# ESC_B.net
KiCad netlist of a schematic drawn in Altium Designer
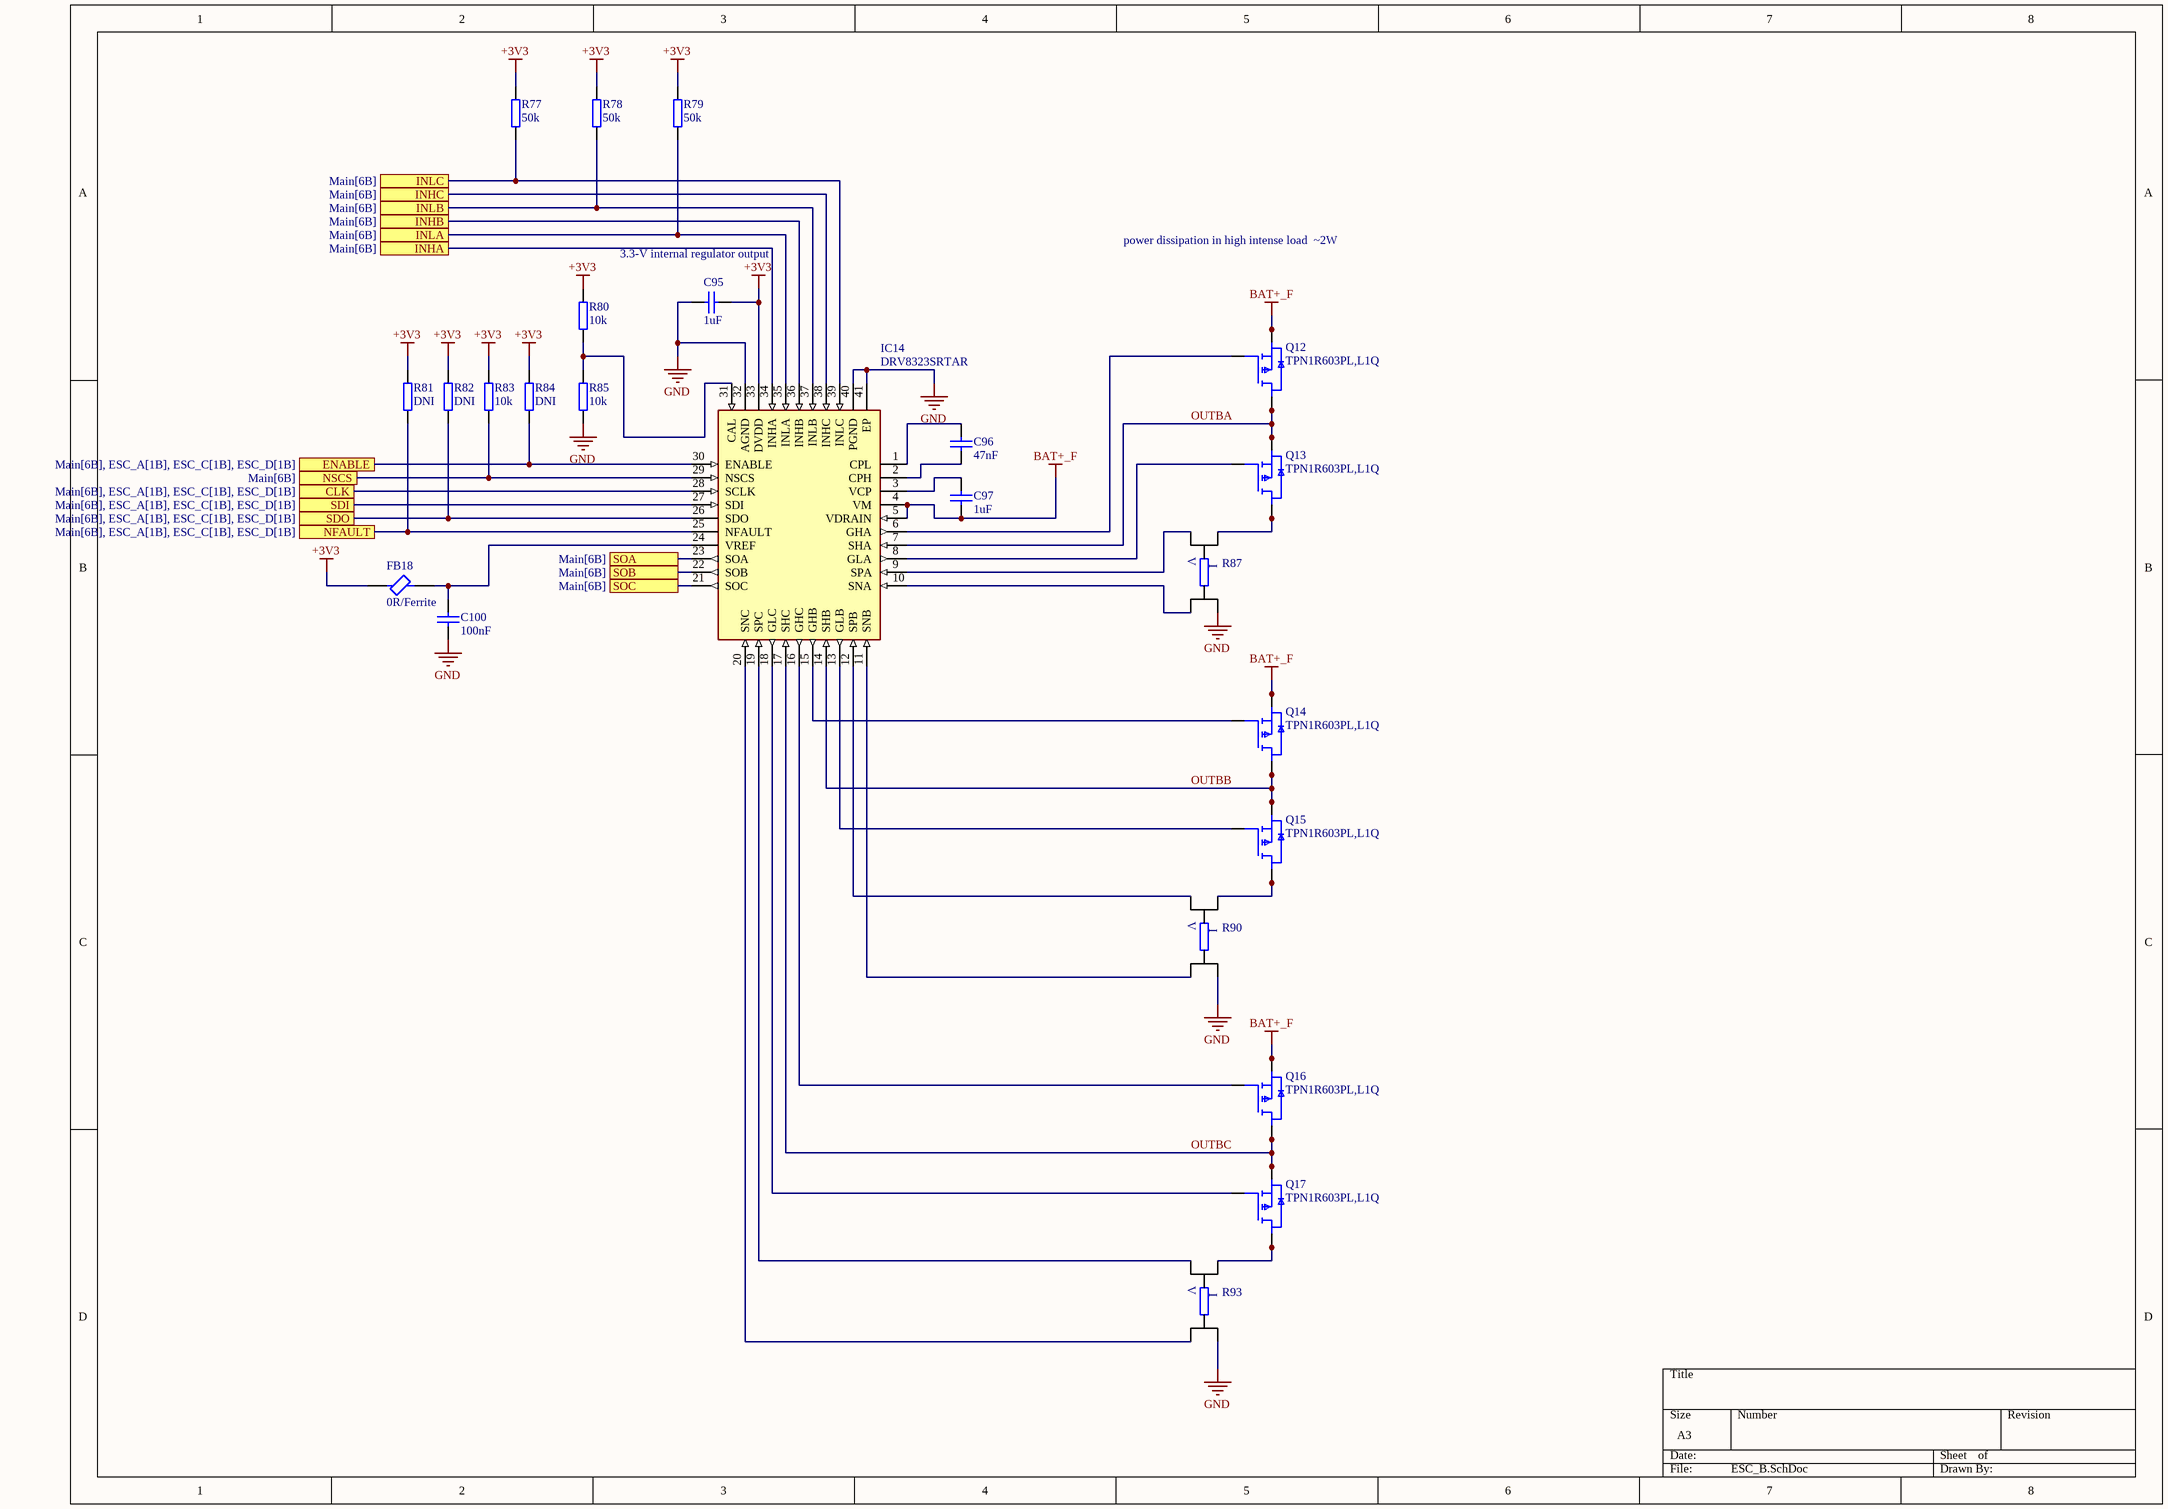
[diagram p0: ESC_B.SchDoc]

(export (version "E")
  (design (tool "Eeschema 10.0.6"))
  (components
    (comp (ref "C95")
      (value "1uF")
      (footprint "CAP0402")
      (fields (field (name "VOLTAGE") "val") (field (name "Comment") "Cap0402"))
      (libsource (lib "capacitorsSMD") (part "Cap0402"))
    )
    (comp (ref "C96")
      (value "47nF")
      (footprint "CAP0603")
      (description "50V")
      (fields (field (name "Comment") "CapSMD0603") (field (name "PUBLISHER") "Altium Limited"))
      (libsource (lib "capacitorsSMD") (part "CapSMD0603"))
    )
    (comp (ref "C97")
      (value "1uF")
      (footprint "CAP0603")
      (description "50V")
      (fields (field (name "Comment") "CapSMD0603") (field (name "PUBLISHER") "Altium Limited"))
      (libsource (lib "capacitorsSMD") (part "CapSMD0603"))
    )
    (comp (ref "C100")
      (value "100nF")
      (footprint "CAP0402")
      (fields (field (name "VOLTAGE") "6V3") (field (name "Comment") "Cap0402"))
      (libsource (lib "capacitorsSMD") (part "Cap0402"))
    )
    (comp (ref "FB18")
      (value "0R/Ferrite")
      (footprint "SamacSys:NFZ15SG152SN10B")
      (description "Ferrite Bead")
      (fields
        (field (name "MANUFACTURER_PART_NUMBER") "BLM15PE471SH1D")
        (field (name "MOUSER PART NUMBER") "81-BLM15PE471SH1D")
      )
      (libsource (lib "SamacSys") (part "BLM15PE471SH1D"))
    )
    (comp (ref "IC14")
      (value "DRV8323SRTAR")
      (footprint "SamacSys:QFN50P600X600X80-41N-D")
      (description "Integrated Circuit")
      (fields (field (name "MOUSER PART NUMBER") "595-DRV8323SRTAR"))
      (libsource (lib "*") (part "DRV8323SRTAR"))
    )
    (comp (ref "Q12")
      (value "TPN1R603PL,L1Q")
      (footprint "SamacSys:TPN1R603PLL1Q")
      (description "MOSFET (N-Channel)")
      (fields (field (name "MOUSER PART NUMBER") "757-TPN1R603PLL1Q"))
      (libsource (lib "SamacSys") (part "TPN1R603PL,L1Q"))
    )
    (comp (ref "Q13")
      (value "TPN1R603PL,L1Q")
      (footprint "SamacSys:TPN1R603PLL1Q")
      (description "MOSFET (N-Channel)")
      (fields (field (name "MOUSER PART NUMBER") "757-TPN1R603PLL1Q"))
      (libsource (lib "SamacSys") (part "TPN1R603PL,L1Q"))
    )
    (comp (ref "Q14")
      (value "TPN1R603PL,L1Q")
      (footprint "SamacSys:TPN1R603PLL1Q")
      (description "MOSFET (N-Channel)")
      (fields (field (name "MOUSER PART NUMBER") "757-TPN1R603PLL1Q"))
      (libsource (lib "SamacSys") (part "TPN1R603PL,L1Q"))
    )
    (comp (ref "Q15")
      (value "TPN1R603PL,L1Q")
      (footprint "SamacSys:TPN1R603PLL1Q")
      (description "MOSFET (N-Channel)")
      (fields (field (name "MOUSER PART NUMBER") "757-TPN1R603PLL1Q"))
      (libsource (lib "SamacSys") (part "TPN1R603PL,L1Q"))
    )
    (comp (ref "Q16")
      (value "TPN1R603PL,L1Q")
      (footprint "SamacSys:TPN1R603PLL1Q")
      (description "MOSFET (N-Channel)")
      (fields (field (name "MOUSER PART NUMBER") "757-TPN1R603PLL1Q"))
      (libsource (lib "SamacSys") (part "TPN1R603PL,L1Q"))
    )
    (comp (ref "Q17")
      (value "TPN1R603PL,L1Q")
      (footprint "SamacSys:TPN1R603PLL1Q")
      (description "MOSFET (N-Channel)")
      (fields (field (name "MOUSER PART NUMBER") "757-TPN1R603PLL1Q"))
      (libsource (lib "SamacSys") (part "TPN1R603PL,L1Q"))
    )
    (comp (ref "R77")
      (value "50k")
      (footprint "RES0402")
      (fields (field (name "Comment") "Res0402"))
      (libsource (lib "resistorSMD") (part "Res0402"))
    )
    (comp (ref "R78")
      (value "50k")
      (footprint "RES0402")
      (fields (field (name "Comment") "Res0402"))
      (libsource (lib "resistorSMD") (part "Res0402"))
    )
    (comp (ref "R79")
      (value "50k")
      (footprint "RES0402")
      (fields (field (name "Comment") "Res0402"))
      (libsource (lib "resistorSMD") (part "Res0402"))
    )
    (comp (ref "R80")
      (value "10k")
      (footprint "RES0402")
      (fields (field (name "Comment") "Res0402"))
      (libsource (lib "resistorSMD") (part "Res0402"))
    )
    (comp (ref "R81")
      (value "DNI")
      (footprint "RES0402")
      (fields (field (name "Comment") "Res0402"))
      (libsource (lib "resistorSMD") (part "Res0402"))
    )
    (comp (ref "R82")
      (value "DNI")
      (footprint "RES0402")
      (fields (field (name "Comment") "Res0402"))
      (libsource (lib "resistorSMD") (part "Res0402"))
    )
    (comp (ref "R83")
      (value "10k")
      (footprint "RES0402")
      (fields (field (name "Comment") "Res0402"))
      (libsource (lib "resistorSMD") (part "Res0402"))
    )
    (comp (ref "R84")
      (value "DNI")
      (footprint "RES0402")
      (fields (field (name "Comment") "Res0402"))
      (libsource (lib "resistorSMD") (part "Res0402"))
    )
    (comp (ref "R85")
      (value "10k")
      (footprint "RES0402")
      (fields (field (name "Comment") "Res0402"))
      (libsource (lib "resistorSMD") (part "Res0402"))
    )
    (comp (ref "R87")
      (value "WSK12161L000FEA")
      (footprint "SamacSys:WSK12161L000FEA")
      (description "Resistor")
      (fields
        (field (name "MANUFACTURER_PART_NUMBER") "WSK1216L5000FEA")
        (field (name "MOUSER PART NUMBER") "71-WSK1216L5000FEA")
      )
      (libsource (lib "SamacSys") (part "WSK1216L5000FEA"))
    )
    (comp (ref "R90")
      (value "WSK12161L000FEA")
      (footprint "SamacSys:WSK12161L000FEA")
      (description "Resistor")
      (fields
        (field (name "MANUFACTURER_PART_NUMBER") "WSK1216L5000FEA")
        (field (name "MOUSER PART NUMBER") "71-WSK1216L5000FEA")
      )
      (libsource (lib "SamacSys") (part "WSK1216L5000FEA"))
    )
    (comp (ref "R93")
      (value "WSK12161L000FEA")
      (footprint "SamacSys:WSK12161L000FEA")
      (description "Resistor")
      (fields
        (field (name "MANUFACTURER_PART_NUMBER") "WSK1216L5000FEA")
        (field (name "MOUSER PART NUMBER") "71-WSK1216L5000FEA")
      )
      (libsource (lib "SamacSys") (part "WSK1216L5000FEA"))
    )
  )
  (nets
    (net (code "1") (name "+3V3") (class "Default")
      (node (ref "C95") (pin "2") (pinfunction "2_2") (pintype "passive"))
      (node (ref "FB18") (pin "1") (pinfunction "1_1") (pintype "passive"))
      (node (ref "IC14") (pin "33") (pinfunction "DVDD_33") (pintype "power_in"))
      (node (ref "R77") (pin "2") (pinfunction "2_2") (pintype "passive"))
      (node (ref "R78") (pin "2") (pinfunction "2_2") (pintype "passive"))
      (node (ref "R79") (pin "2") (pinfunction "2_2") (pintype "passive"))
      (node (ref "R80") (pin "2") (pinfunction "2_2") (pintype "passive"))
      (node (ref "R81") (pin "2") (pinfunction "2_2") (pintype "passive"))
      (node (ref "R82") (pin "2") (pinfunction "2_2") (pintype "passive"))
      (node (ref "R83") (pin "2") (pinfunction "2_2") (pintype "passive"))
      (node (ref "R84") (pin "2") (pinfunction "2_2") (pintype "passive"))
    )
    (net (code "2") (name "/CLK") (class "Default")
      (node (ref "IC14") (pin "28") (pinfunction "SCLK_28") (pintype "input"))
    )
    (net (code "3") (name "/ENABLE") (class "Default")
      (node (ref "IC14") (pin "30") (pinfunction "ENABLE_30") (pintype "input"))
      (node (ref "R84") (pin "1") (pinfunction "1_1") (pintype "passive"))
    )
    (net (code "4") (name "/INHA") (class "Default")
      (node (ref "IC14") (pin "34") (pinfunction "INHA_34") (pintype "input"))
    )
    (net (code "5") (name "/INHB") (class "Default")
      (node (ref "IC14") (pin "36") (pinfunction "INHB_36") (pintype "input"))
    )
    (net (code "6") (name "/INHC") (class "Default")
      (node (ref "IC14") (pin "38") (pinfunction "INHC_38") (pintype "input"))
    )
    (net (code "7") (name "/INLA") (class "Default")
      (node (ref "IC14") (pin "35") (pinfunction "INLA_35") (pintype "input"))
      (node (ref "R79") (pin "1") (pinfunction "1_1") (pintype "passive"))
    )
    (net (code "8") (name "/INLB") (class "Default")
      (node (ref "IC14") (pin "37") (pinfunction "INLB_37") (pintype "input"))
      (node (ref "R78") (pin "1") (pinfunction "1_1") (pintype "passive"))
    )
    (net (code "9") (name "/INLC") (class "Default")
      (node (ref "IC14") (pin "39") (pinfunction "INLC_39") (pintype "input"))
      (node (ref "R77") (pin "1") (pinfunction "1_1") (pintype "passive"))
    )
    (net (code "10") (name "/NFAULT") (class "Default")
      (node (ref "IC14") (pin "25") (pinfunction "NFAULT_25") (pintype "passive"))
      (node (ref "R81") (pin "1") (pinfunction "1_1") (pintype "passive"))
    )
    (net (code "11") (name "/NSCS") (class "Default")
      (node (ref "IC14") (pin "29") (pinfunction "NSCS_29") (pintype "input"))
      (node (ref "R83") (pin "1") (pinfunction "1_1") (pintype "passive"))
    )
    (net (code "12") (name "/OUTBA") (class "Default")
      (node (ref "IC14") (pin "7") (pinfunction "SHA_7") (pintype "input"))
      (node (ref "Q12") (pin "5") (pinfunction "D_1_5") (pintype "passive"))
      (node (ref "Q12") (pin "6") (pinfunction "D_2_6") (pintype "passive"))
      (node (ref "Q12") (pin "7") (pinfunction "D_3_7") (pintype "passive"))
      (node (ref "Q12") (pin "8") (pinfunction "D_4_8") (pintype "passive"))
      (node (ref "Q12") (pin "9") (pinfunction "D_4_9") (pintype "passive"))
      (node (ref "Q13") (pin "1") (pinfunction "S_1_1") (pintype "passive"))
      (node (ref "Q13") (pin "2") (pinfunction "S_2_2") (pintype "passive"))
      (node (ref "Q13") (pin "3") (pinfunction "S_3_3") (pintype "passive"))
    )
    (net (code "13") (name "/OUTBB") (class "Default")
      (node (ref "IC14") (pin "14") (pinfunction "SHB_14") (pintype "input"))
      (node (ref "Q14") (pin "5") (pinfunction "D_1_5") (pintype "passive"))
      (node (ref "Q14") (pin "6") (pinfunction "D_2_6") (pintype "passive"))
      (node (ref "Q14") (pin "7") (pinfunction "D_3_7") (pintype "passive"))
      (node (ref "Q14") (pin "8") (pinfunction "D_4_8") (pintype "passive"))
      (node (ref "Q14") (pin "9") (pinfunction "D_4_9") (pintype "passive"))
      (node (ref "Q15") (pin "1") (pinfunction "S_1_1") (pintype "passive"))
      (node (ref "Q15") (pin "2") (pinfunction "S_2_2") (pintype "passive"))
      (node (ref "Q15") (pin "3") (pinfunction "S_3_3") (pintype "passive"))
    )
    (net (code "14") (name "/OUTBC") (class "Default")
      (node (ref "IC14") (pin "17") (pinfunction "SHC_17") (pintype "input"))
      (node (ref "Q16") (pin "5") (pinfunction "D_1_5") (pintype "passive"))
      (node (ref "Q16") (pin "6") (pinfunction "D_2_6") (pintype "passive"))
      (node (ref "Q16") (pin "7") (pinfunction "D_3_7") (pintype "passive"))
      (node (ref "Q16") (pin "8") (pinfunction "D_4_8") (pintype "passive"))
      (node (ref "Q16") (pin "9") (pinfunction "D_4_9") (pintype "passive"))
      (node (ref "Q17") (pin "1") (pinfunction "S_1_1") (pintype "passive"))
      (node (ref "Q17") (pin "2") (pinfunction "S_2_2") (pintype "passive"))
      (node (ref "Q17") (pin "3") (pinfunction "S_3_3") (pintype "passive"))
    )
    (net (code "15") (name "/SDI") (class "Default")
      (node (ref "IC14") (pin "27") (pinfunction "SDI_27") (pintype "input"))
    )
    (net (code "16") (name "/SDO") (class "Default")
      (node (ref "IC14") (pin "26") (pinfunction "SDO_26") (pintype "passive"))
      (node (ref "R82") (pin "1") (pinfunction "1_1") (pintype "passive"))
    )
    (net (code "17") (name "/SOA") (class "Default")
      (node (ref "IC14") (pin "23") (pinfunction "SOA_23") (pintype "output"))
    )
    (net (code "18") (name "/SOB") (class "Default")
      (node (ref "IC14") (pin "22") (pinfunction "SOB_22") (pintype "output"))
    )
    (net (code "19") (name "/SOC") (class "Default")
      (node (ref "IC14") (pin "21") (pinfunction "SOC_21") (pintype "output"))
    )
    (net (code "20") (name "BAT+_F") (class "Default")
      (node (ref "C97") (pin "1") (pinfunction "1_1") (pintype "passive"))
      (node (ref "IC14") (pin "4") (pinfunction "VM_4") (pintype "power_in"))
      (node (ref "IC14") (pin "5") (pinfunction "VDRAIN_5") (pintype "input"))
      (node (ref "Q12") (pin "1") (pinfunction "S_1_1") (pintype "passive"))
      (node (ref "Q12") (pin "2") (pinfunction "S_2_2") (pintype "passive"))
      (node (ref "Q12") (pin "3") (pinfunction "S_3_3") (pintype "passive"))
      (node (ref "Q14") (pin "1") (pinfunction "S_1_1") (pintype "passive"))
      (node (ref "Q14") (pin "2") (pinfunction "S_2_2") (pintype "passive"))
      (node (ref "Q14") (pin "3") (pinfunction "S_3_3") (pintype "passive"))
      (node (ref "Q16") (pin "1") (pinfunction "S_1_1") (pintype "passive"))
      (node (ref "Q16") (pin "2") (pinfunction "S_2_2") (pintype "passive"))
      (node (ref "Q16") (pin "3") (pinfunction "S_3_3") (pintype "passive"))
    )
    (net (code "21") (name "GND") (class "Default")
      (node (ref "C100") (pin "1") (pinfunction "1_1") (pintype "passive"))
      (node (ref "C95") (pin "1") (pinfunction "1_1") (pintype "passive"))
      (node (ref "IC14") (pin "32") (pinfunction "AGND_32") (pintype "power_in"))
      (node (ref "IC14") (pin "40") (pinfunction "PGND_40") (pintype "power_in"))
      (node (ref "IC14") (pin "41") (pinfunction "EP_41") (pintype "power_in"))
      (node (ref "R85") (pin "1") (pinfunction "1_1") (pintype "passive"))
      (node (ref "R87") (pin "4") (pinfunction "4_4") (pintype "passive"))
      (node (ref "R90") (pin "4") (pinfunction "4_4") (pintype "passive"))
      (node (ref "R93") (pin "4") (pinfunction "4_4") (pintype "passive"))
    )
    (net (code "22") (name "Net-(IC14-CAL)") (class "Default")
      (node (ref "IC14") (pin "31") (pinfunction "CAL_31") (pintype "input"))
      (node (ref "R80") (pin "1") (pinfunction "1_1") (pintype "passive"))
      (node (ref "R85") (pin "2") (pinfunction "2_2") (pintype "passive"))
    )
    (net (code "23") (name "Net-(IC14-CPH)") (class "Default")
      (node (ref "C96") (pin "1") (pinfunction "1_1") (pintype "passive"))
      (node (ref "IC14") (pin "2") (pinfunction "CPH_2") (pintype "power_in"))
    )
    (net (code "24") (name "Net-(IC14-CPL)") (class "Default")
      (node (ref "C96") (pin "2") (pinfunction "2_2") (pintype "passive"))
      (node (ref "IC14") (pin "1") (pinfunction "CPL_1") (pintype "power_in"))
    )
    (net (code "25") (name "Net-(IC14-GHA)") (class "Default")
      (node (ref "IC14") (pin "6") (pinfunction "GHA_6") (pintype "output"))
      (node (ref "Q12") (pin "4") (pinfunction "G_4") (pintype "passive"))
    )
    (net (code "26") (name "Net-(IC14-GHB)") (class "Default")
      (node (ref "IC14") (pin "15") (pinfunction "GHB_15") (pintype "output"))
      (node (ref "Q14") (pin "4") (pinfunction "G_4") (pintype "passive"))
    )
    (net (code "27") (name "Net-(IC14-GHC)") (class "Default")
      (node (ref "IC14") (pin "16") (pinfunction "GHC_16") (pintype "output"))
      (node (ref "Q16") (pin "4") (pinfunction "G_4") (pintype "passive"))
    )
    (net (code "28") (name "Net-(IC14-GLA)") (class "Default")
      (node (ref "IC14") (pin "8") (pinfunction "GLA_8") (pintype "output"))
      (node (ref "Q13") (pin "4") (pinfunction "G_4") (pintype "passive"))
    )
    (net (code "29") (name "Net-(IC14-GLB)") (class "Default")
      (node (ref "IC14") (pin "13") (pinfunction "GLB_13") (pintype "output"))
      (node (ref "Q15") (pin "4") (pinfunction "G_4") (pintype "passive"))
    )
    (net (code "30") (name "Net-(IC14-GLC)") (class "Default")
      (node (ref "IC14") (pin "18") (pinfunction "GLC_18") (pintype "output"))
      (node (ref "Q17") (pin "4") (pinfunction "G_4") (pintype "passive"))
    )
    (net (code "31") (name "Net-(IC14-SNA)") (class "Default")
      (node (ref "IC14") (pin "10") (pinfunction "SNA_10") (pintype "input"))
      (node (ref "R87") (pin "3") (pinfunction "3_3") (pintype "passive"))
    )
    (net (code "32") (name "Net-(IC14-SNB)") (class "Default")
      (node (ref "IC14") (pin "11") (pinfunction "SNB_11") (pintype "input"))
      (node (ref "R90") (pin "3") (pinfunction "3_3") (pintype "passive"))
    )
    (net (code "33") (name "Net-(IC14-SNC)") (class "Default")
      (node (ref "IC14") (pin "20") (pinfunction "SNC_20") (pintype "input"))
      (node (ref "R93") (pin "3") (pinfunction "3_3") (pintype "passive"))
    )
    (net (code "34") (name "Net-(IC14-SPA)") (class "Default")
      (node (ref "IC14") (pin "9") (pinfunction "SPA_9") (pintype "input"))
      (node (ref "R87") (pin "2") (pinfunction "2_2") (pintype "passive"))
    )
    (net (code "35") (name "Net-(IC14-SPB)") (class "Default")
      (node (ref "IC14") (pin "12") (pinfunction "SPB_12") (pintype "input"))
      (node (ref "R90") (pin "2") (pinfunction "2_2") (pintype "passive"))
    )
    (net (code "36") (name "Net-(IC14-SPC)") (class "Default")
      (node (ref "IC14") (pin "19") (pinfunction "SPC_19") (pintype "input"))
      (node (ref "R93") (pin "2") (pinfunction "2_2") (pintype "passive"))
    )
    (net (code "37") (name "Net-(IC14-VCP)") (class "Default")
      (node (ref "C97") (pin "2") (pinfunction "2_2") (pintype "passive"))
      (node (ref "IC14") (pin "3") (pinfunction "VCP_3") (pintype "power_in"))
    )
    (net (code "38") (name "Net-(IC14-VREF)") (class "Default")
      (node (ref "C100") (pin "2") (pinfunction "2_2") (pintype "passive"))
      (node (ref "FB18") (pin "2") (pinfunction "2_2") (pintype "passive"))
      (node (ref "IC14") (pin "24") (pinfunction "VREF_24") (pintype "power_in"))
    )
    (net (code "39") (name "Net-(Q13-D_1)") (class "Default")
      (node (ref "Q13") (pin "5") (pinfunction "D_1_5") (pintype "passive"))
      (node (ref "Q13") (pin "6") (pinfunction "D_2_6") (pintype "passive"))
      (node (ref "Q13") (pin "7") (pinfunction "D_3_7") (pintype "passive"))
      (node (ref "Q13") (pin "8") (pinfunction "D_4_8") (pintype "passive"))
      (node (ref "Q13") (pin "9") (pinfunction "D_4_9") (pintype "passive"))
      (node (ref "R87") (pin "1") (pinfunction "1_1") (pintype "passive"))
    )
    (net (code "40") (name "Net-(Q15-D_1)") (class "Default")
      (node (ref "Q15") (pin "5") (pinfunction "D_1_5") (pintype "passive"))
      (node (ref "Q15") (pin "6") (pinfunction "D_2_6") (pintype "passive"))
      (node (ref "Q15") (pin "7") (pinfunction "D_3_7") (pintype "passive"))
      (node (ref "Q15") (pin "8") (pinfunction "D_4_8") (pintype "passive"))
      (node (ref "Q15") (pin "9") (pinfunction "D_4_9") (pintype "passive"))
      (node (ref "R90") (pin "1") (pinfunction "1_1") (pintype "passive"))
    )
    (net (code "41") (name "Net-(Q17-D_1)") (class "Default")
      (node (ref "Q17") (pin "5") (pinfunction "D_1_5") (pintype "passive"))
      (node (ref "Q17") (pin "6") (pinfunction "D_2_6") (pintype "passive"))
      (node (ref "Q17") (pin "7") (pinfunction "D_3_7") (pintype "passive"))
      (node (ref "Q17") (pin "8") (pinfunction "D_4_8") (pintype "passive"))
      (node (ref "Q17") (pin "9") (pinfunction "D_4_9") (pintype "passive"))
      (node (ref "R93") (pin "1") (pinfunction "1_1") (pintype "passive"))
    )
  )
)
